# 328_smt_testing.net
KiCad netlist of a schematic drawn in EAGLE
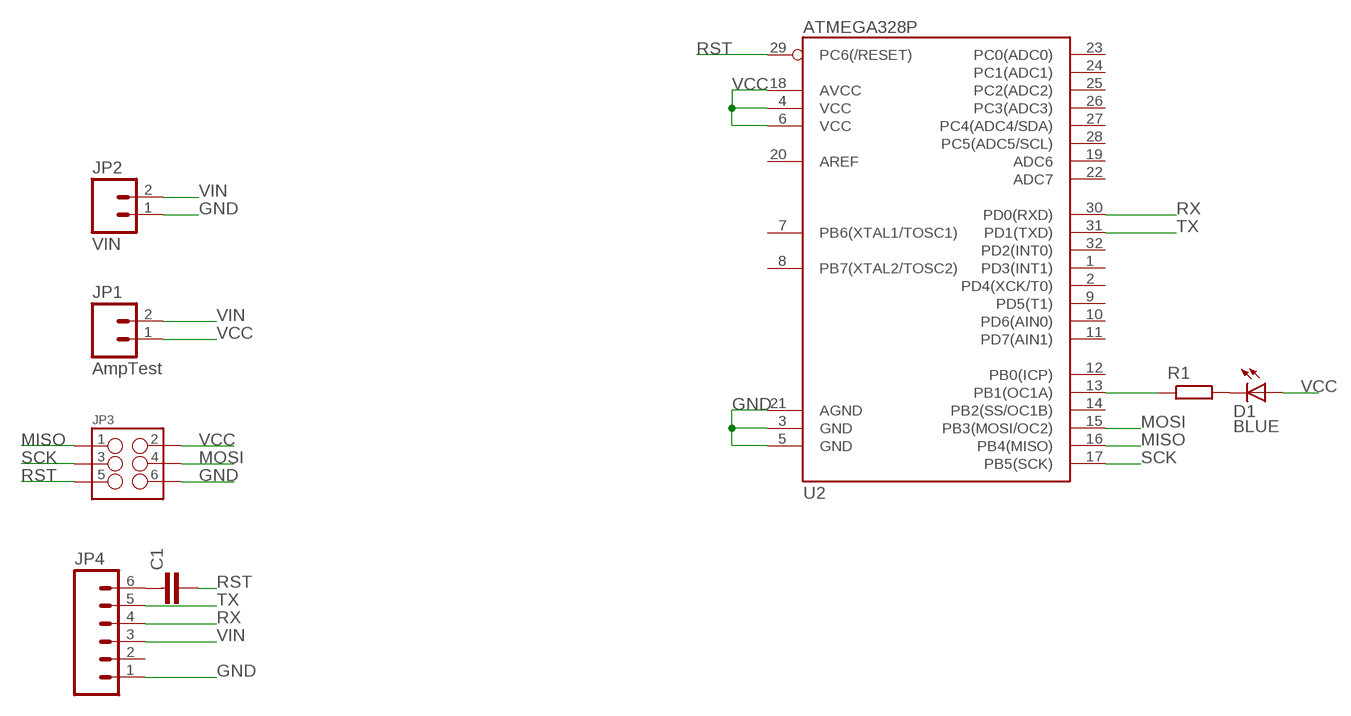
[diagram p0: schematic, sheet 1]

(export (version "E")
  (design (tool "Eeschema 10.0.6"))
  (components
    (comp (ref "C1")
      (value "CAPACITOR0603-N")
      (footprint "eagle-import:C0603-N")
      (libsource (lib "eagle-import") (part "CAPACITOR0603-N"))
    )
    (comp (ref "D1")
      (value "BLUE")
      (footprint "eagle-import:LED-0603")
      (libsource (lib "eagle-import") (part "LED-BLUE0603"))
    )
    (comp (ref "JP1")
      (value "AmpTest")
      (footprint "eagle-import:1X02_LOCK_LONGPADS")
      (libsource (lib "eagle-import") (part "M02LOCK_LONGPADS"))
    )
    (comp (ref "JP2")
      (value "VIN")
      (footprint "eagle-import:1X02_LOCK_LONGPADS")
      (libsource (lib "eagle-import") (part "M02LOCK_LONGPADS"))
    )
    (comp (ref "JP3")
      (value "M03X2FEMALE_SMD")
      (footprint "eagle-import:2X3_SMD")
      (libsource (lib "eagle-import") (part "M03X2FEMALE_SMD"))
    )
    (comp (ref "JP4")
      (value "M06LOCK_LONGPADS")
      (footprint "eagle-import:1X06_LOCK_LONGPADS")
      (libsource (lib "eagle-import") (part "M06LOCK_LONGPADS"))
    )
    (comp (ref "R1")
      (value "RESISTOR0603-L")
      (footprint "eagle-import:R0603-L")
      (libsource (lib "eagle-import") (part "RESISTOR0603-L"))
    )
    (comp (ref "U2")
      (value "ATMEGA328P")
      (footprint "eagle-import:TQFP32-08")
      (libsource (lib "eagle-import") (part "ATMEGA328_SMT"))
    )
  )
  (nets
    (net (code "1") (name "/GND") (class "Default")
      (node (ref "JP2") (pin "1") (pinfunction "1_1") (pintype "passive"))
      (node (ref "JP3") (pin "6") (pinfunction "6_6") (pintype "bidirectional"))
      (node (ref "JP4") (pin "1") (pinfunction "1_1") (pintype "passive"))
      (node (ref "U2") (pin "21") (pinfunction "AGND_21") (pintype "bidirectional"))
      (node (ref "U2") (pin "3") (pinfunction "GND_3") (pintype "bidirectional"))
      (node (ref "U2") (pin "5") (pinfunction "GND_5") (pintype "bidirectional"))
    )
    (net (code "2") (name "/MISO") (class "Default")
      (node (ref "JP3") (pin "1") (pinfunction "1_1") (pintype "bidirectional"))
      (node (ref "U2") (pin "16") (pinfunction "PB4(MISO)_16") (pintype "bidirectional"))
    )
    (net (code "3") (name "/MOSI") (class "Default")
      (node (ref "JP3") (pin "4") (pinfunction "4_4") (pintype "bidirectional"))
      (node (ref "U2") (pin "15") (pinfunction "PB3(MOSI/OC2)_15") (pintype "bidirectional"))
    )
    (net (code "4") (name "/RST") (class "Default")
      (node (ref "C1") (pin "2") (pinfunction "2_2") (pintype "passive"))
      (node (ref "JP3") (pin "5") (pinfunction "5_5") (pintype "bidirectional"))
      (node (ref "U2") (pin "29") (pinfunction "PC6(/RESET)_29") (pintype "bidirectional"))
    )
    (net (code "5") (name "/RX") (class "Default")
      (node (ref "JP4") (pin "4") (pinfunction "4_4") (pintype "passive"))
      (node (ref "U2") (pin "30") (pinfunction "PD0(RXD)_30") (pintype "bidirectional"))
    )
    (net (code "6") (name "/SCK") (class "Default")
      (node (ref "JP3") (pin "3") (pinfunction "3_3") (pintype "bidirectional"))
      (node (ref "U2") (pin "17") (pinfunction "PB5(SCK)_17") (pintype "bidirectional"))
    )
    (net (code "7") (name "/TX") (class "Default")
      (node (ref "JP4") (pin "5") (pinfunction "5_5") (pintype "passive"))
      (node (ref "U2") (pin "31") (pinfunction "PD1(TXD)_31") (pintype "bidirectional"))
    )
    (net (code "8") (name "/VCC") (class "Default")
      (node (ref "D1") (pin "A") (pinfunction "A_A") (pintype "passive"))
      (node (ref "JP1") (pin "1") (pinfunction "1_1") (pintype "passive"))
      (node (ref "JP3") (pin "2") (pinfunction "2_2") (pintype "bidirectional"))
      (node (ref "U2") (pin "18") (pinfunction "AVCC_18") (pintype "bidirectional"))
      (node (ref "U2") (pin "4") (pinfunction "VCC_4") (pintype "bidirectional"))
      (node (ref "U2") (pin "6") (pinfunction "VCC_6") (pintype "bidirectional"))
    )
    (net (code "9") (name "/VIN") (class "Default")
      (node (ref "JP1") (pin "2") (pinfunction "2_2") (pintype "passive"))
      (node (ref "JP2") (pin "2") (pinfunction "2_2") (pintype "passive"))
      (node (ref "JP4") (pin "3") (pinfunction "3_3") (pintype "passive"))
    )
    (net (code "10") (name "Net-(C1-Pad1)") (class "Default")
      (node (ref "C1") (pin "1") (pinfunction "1_1") (pintype "passive"))
      (node (ref "JP4") (pin "6") (pinfunction "6_6") (pintype "passive"))
    )
    (net (code "11") (name "Net-(R1-P$1)") (class "Default")
      (node (ref "R1") (pin "1") (pinfunction "P$1_1") (pintype "passive"))
      (node (ref "U2") (pin "13") (pinfunction "PB1(OC1A)_13") (pintype "bidirectional"))
    )
    (net (code "12") (name "Net-(R1-P$2)") (class "Default")
      (node (ref "D1") (pin "C") (pinfunction "C_C") (pintype "passive"))
      (node (ref "R1") (pin "2") (pinfunction "P$2_2") (pintype "passive"))
    )
    (net (code "13") (name "unconnected-(JP4-Pad2)") (class "Default")
      (node (ref "JP4") (pin "2") (pinfunction "2_2") (pintype "passive"))
    )
    (net (code "14") (name "unconnected-(U2-ADC6-Pad19)") (class "Default")
      (node (ref "U2") (pin "19") (pinfunction "ADC6_19") (pintype "bidirectional"))
    )
    (net (code "15") (name "unconnected-(U2-ADC7-Pad22)") (class "Default")
      (node (ref "U2") (pin "22") (pinfunction "ADC7_22") (pintype "bidirectional"))
    )
    (net (code "16") (name "unconnected-(U2-AREF-Pad20)") (class "Default")
      (node (ref "U2") (pin "20") (pinfunction "AREF_20") (pintype "bidirectional"))
    )
    (net (code "17") (name "unconnected-(U2-PB0(ICP)-Pad12)") (class "Default")
      (node (ref "U2") (pin "12") (pinfunction "PB0(ICP)_12") (pintype "bidirectional"))
    )
    (net (code "18") (name "unconnected-(U2-PB2(SS{slash}OC1B)-Pad14)") (class "Default")
      (node (ref "U2") (pin "14") (pinfunction "PB2(SS/OC1B)_14") (pintype "bidirectional"))
    )
    (net (code "19") (name "unconnected-(U2-PB6(XTAL1{slash}TOSC1)-Pad7)") (class "Default")
      (node (ref "U2") (pin "7") (pinfunction "PB6(XTAL1/TOSC1)_7") (pintype "bidirectional"))
    )
    (net (code "20") (name "unconnected-(U2-PB7(XTAL2{slash}TOSC2)-Pad8)") (class "Default")
      (node (ref "U2") (pin "8") (pinfunction "PB7(XTAL2/TOSC2)_8") (pintype "bidirectional"))
    )
    (net (code "21") (name "unconnected-(U2-PC0(ADC0)-Pad23)") (class "Default")
      (node (ref "U2") (pin "23") (pinfunction "PC0(ADC0)_23") (pintype "bidirectional"))
    )
    (net (code "22") (name "unconnected-(U2-PC1(ADC1)-Pad24)") (class "Default")
      (node (ref "U2") (pin "24") (pinfunction "PC1(ADC1)_24") (pintype "bidirectional"))
    )
    (net (code "23") (name "unconnected-(U2-PC2(ADC2)-Pad25)") (class "Default")
      (node (ref "U2") (pin "25") (pinfunction "PC2(ADC2)_25") (pintype "bidirectional"))
    )
    (net (code "24") (name "unconnected-(U2-PC3(ADC3)-Pad26)") (class "Default")
      (node (ref "U2") (pin "26") (pinfunction "PC3(ADC3)_26") (pintype "bidirectional"))
    )
    (net (code "25") (name "unconnected-(U2-PC4(ADC4{slash}SDA)-Pad27)") (class "Default")
      (node (ref "U2") (pin "27") (pinfunction "PC4(ADC4/SDA)_27") (pintype "bidirectional"))
    )
    (net (code "26") (name "unconnected-(U2-PC5(ADC5{slash}SCL)-Pad28)") (class "Default")
      (node (ref "U2") (pin "28") (pinfunction "PC5(ADC5/SCL)_28") (pintype "bidirectional"))
    )
    (net (code "27") (name "unconnected-(U2-PD2(INT0)-Pad32)") (class "Default")
      (node (ref "U2") (pin "32") (pinfunction "PD2(INT0)_32") (pintype "bidirectional"))
    )
    (net (code "28") (name "unconnected-(U2-PD3(INT1)-Pad1)") (class "Default")
      (node (ref "U2") (pin "1") (pinfunction "PD3(INT1)_1") (pintype "bidirectional"))
    )
    (net (code "29") (name "unconnected-(U2-PD4(XCK{slash}T0)-Pad2)") (class "Default")
      (node (ref "U2") (pin "2") (pinfunction "PD4(XCK/T0)_2") (pintype "bidirectional"))
    )
    (net (code "30") (name "unconnected-(U2-PD5(T1)-Pad9)") (class "Default")
      (node (ref "U2") (pin "9") (pinfunction "PD5(T1)_9") (pintype "bidirectional"))
    )
    (net (code "31") (name "unconnected-(U2-PD6(AIN0)-Pad10)") (class "Default")
      (node (ref "U2") (pin "10") (pinfunction "PD6(AIN0)_10") (pintype "bidirectional"))
    )
    (net (code "32") (name "unconnected-(U2-PD7(AIN1)-Pad11)") (class "Default")
      (node (ref "U2") (pin "11") (pinfunction "PD7(AIN1)_11") (pintype "bidirectional"))
    )
  )
)
